# Drawdio.net
KiCad netlist of a schematic drawn in Altium Designer
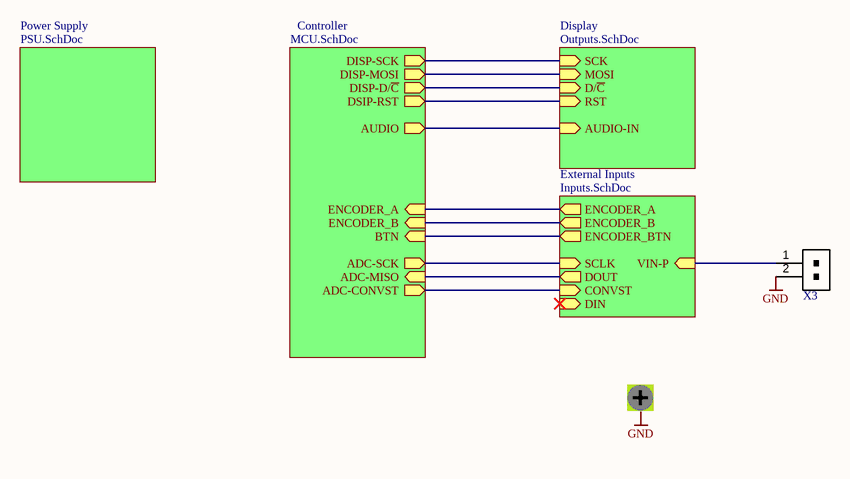
[diagram p0: Drawdio.SchDoc]

(export (version "E")
  (design (tool "Eeschema 10.0.6"))
  (components
    (comp (ref "MH1")
      (value "MECH - M2 screw")
      (footprint "MECH-M2 - no screw")
      (description "M3 hole with screw")
      (libsource (lib "MasterLib") (part "MECH - M2 screw"))
    )
    (comp (ref "X3")
      (value "CONN - 2P -THT-JST 2.00mm")
      (footprint "CONN-2P-THT-RIGHT-JST 2.00mm")
      (description "1x2 pin THT connector")
      (libsource (lib "MasterLib") (part "CONN - 2P -THT-JST 2.00mm"))
    )
  )
  (nets
    (net (code "13") (name "/VIN-P") (class "Default")
      (node (ref "X3") (pin "1") (pinfunction "1_1") (pintype "passive"))
    )
    (net (code "14") (name "GND") (class "Default")
      (node (ref "MH1") (pin "MH") (pinfunction "Con_MH") (pintype "passive"))
      (node (ref "X3") (pin "2") (pinfunction "2_2") (pintype "passive"))
    )
  )
)
